# GPRSshield_V2.net
KiCad netlist of a schematic drawn in EAGLE
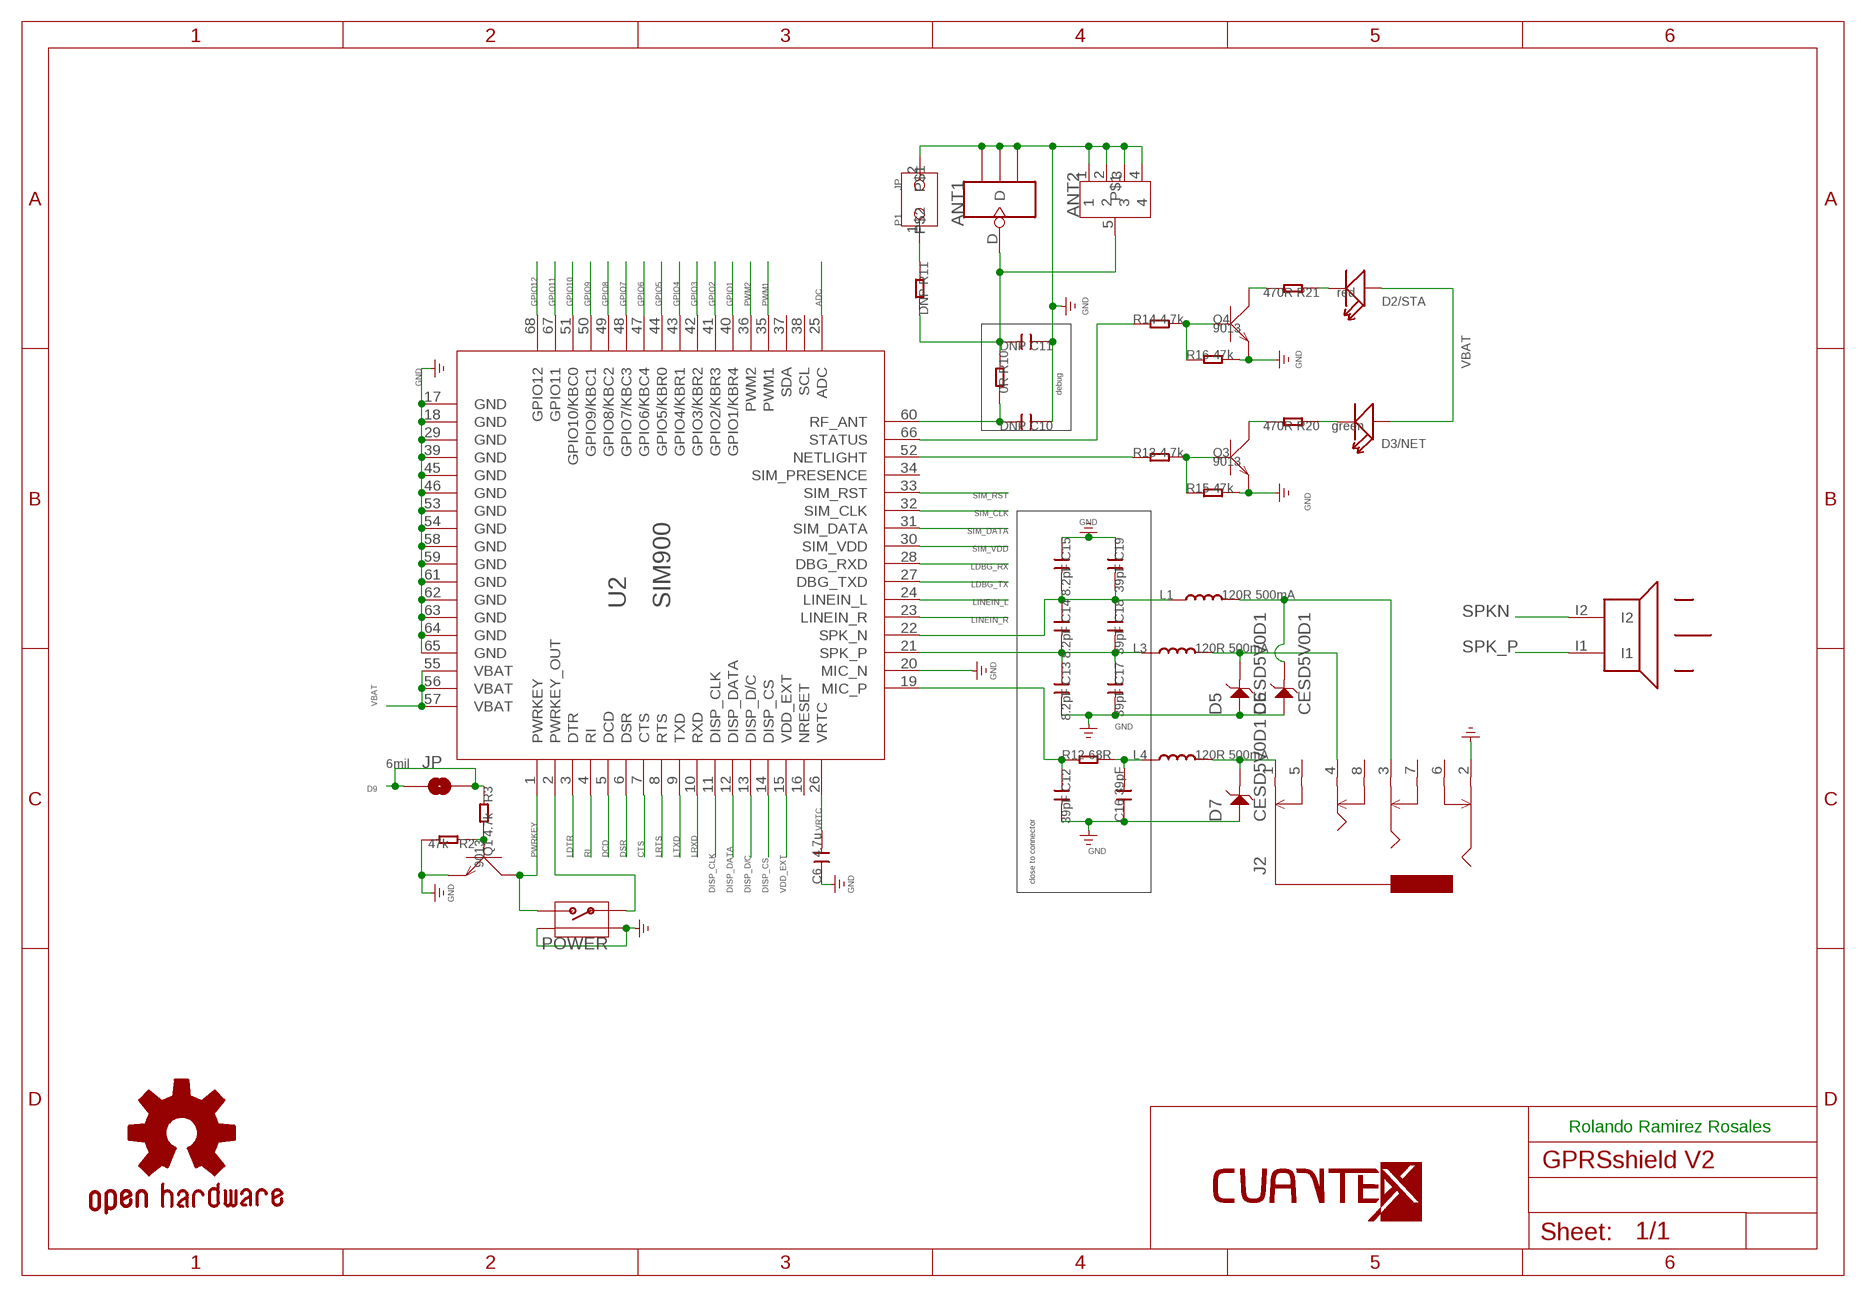
[diagram p0: schematic, sheet 1, part 1 of 2]
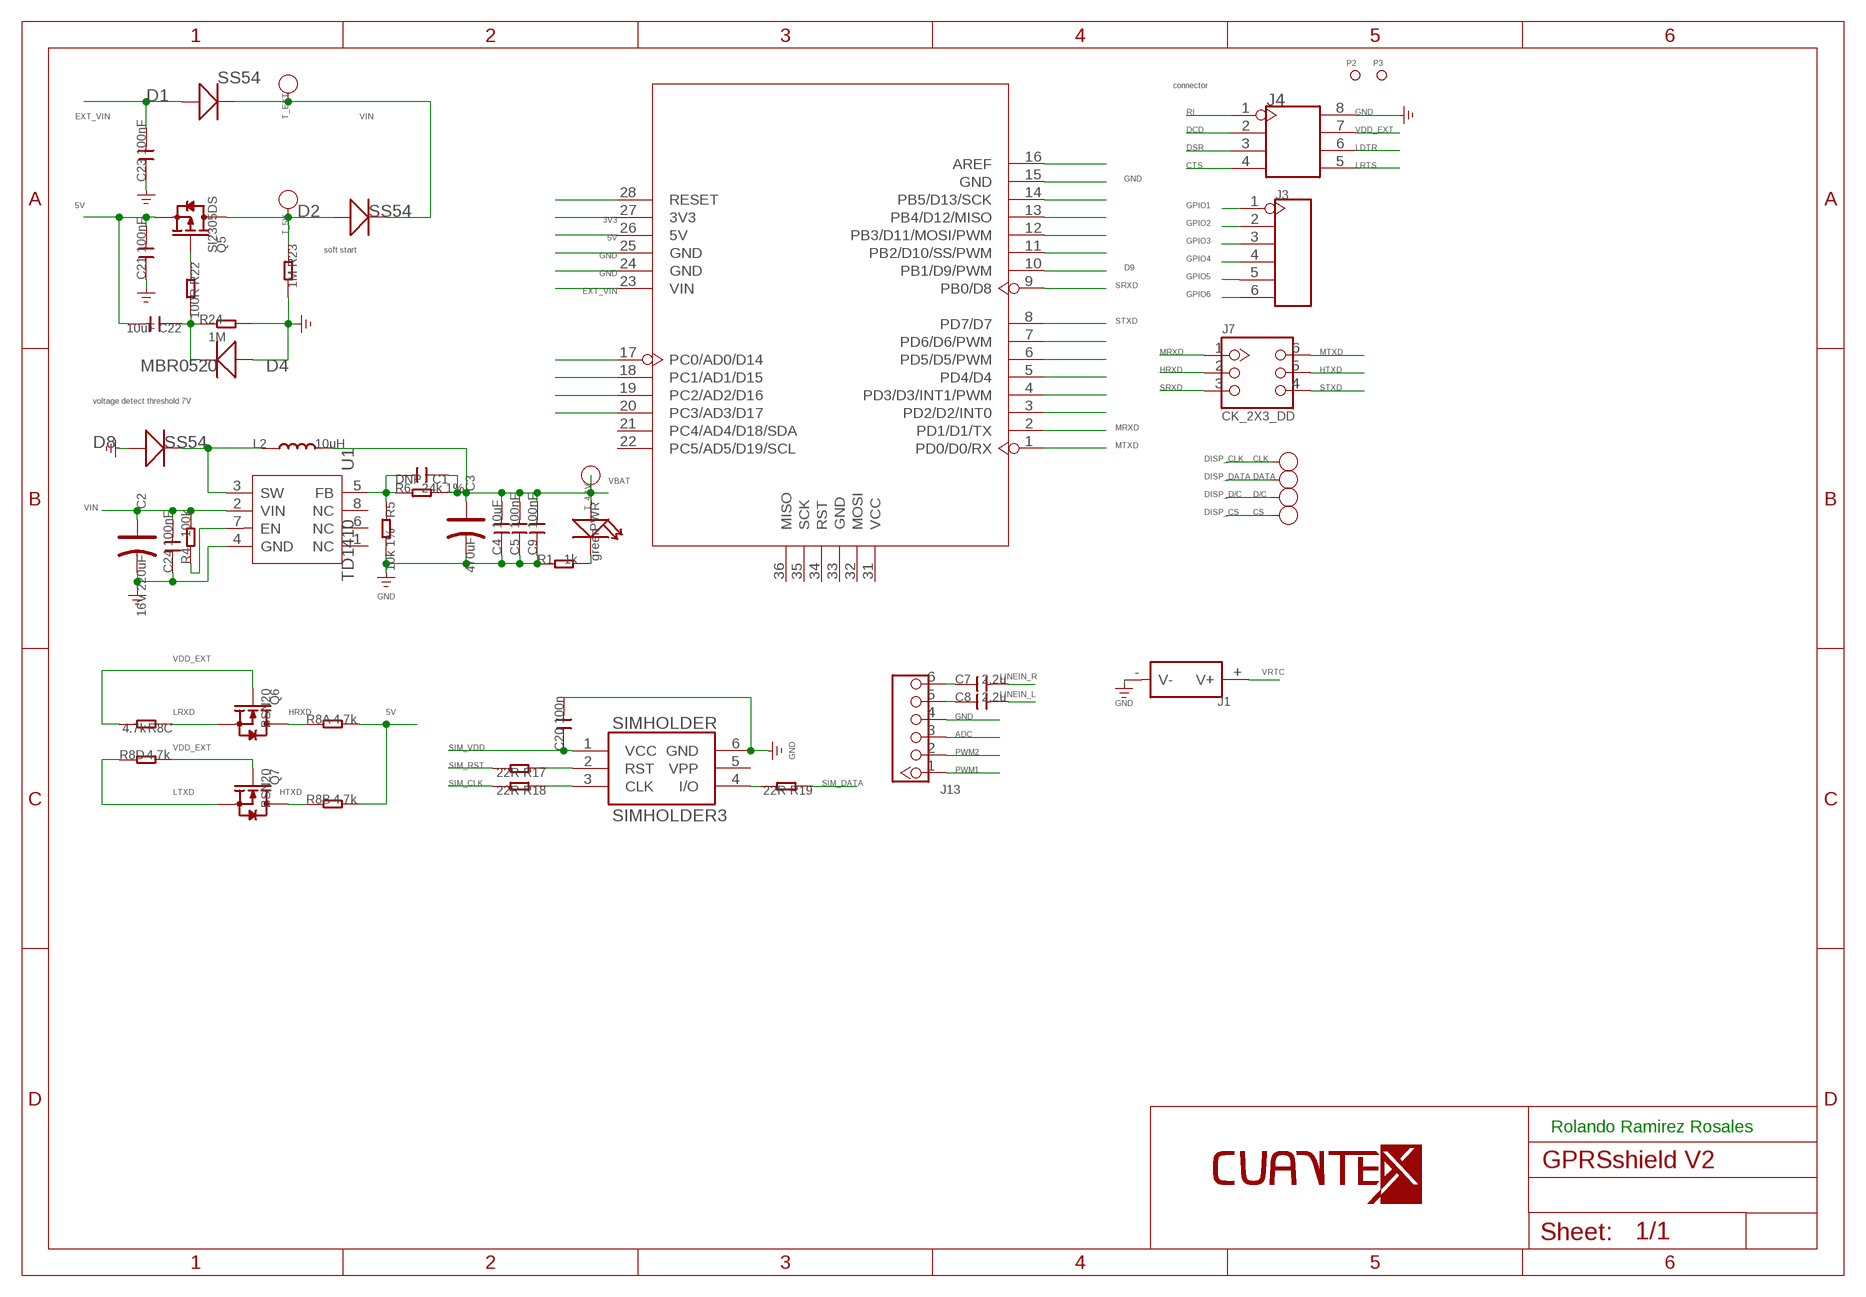
[diagram p1: schematic, sheet 1, part 2 of 2]

(export (version "E")
  (design (tool "Eeschema 10.0.6"))
  (components
    (comp (ref "ANT1")
      (value "ANTENNA-U-FL")
      (footprint "eagle-import:4P-U-FL")
      (libsource (lib "eagle-import") (part "ANTENNA-U-FL"))
    )
    (comp (ref "ANT2")
      (value "ANTENNA-SMA-IPX")
      (footprint "eagle-import:SMA-TO-IPX")
      (libsource (lib "eagle-import") (part "ANTENNA-SMA-IPX"))
    )
    (comp (ref "C1")
      (value "DNP")
      (footprint "eagle-import:C0603")
      (libsource (lib "eagle-import") (part "C-0603"))
    )
    (comp (ref "C2")
      (value "16V 220uF")
      (footprint "eagle-import:ELECTRO-SMD-D-5.6MM")
      (libsource (lib "eagle-import") (part "CAP-ELECTRO-D"))
    )
    (comp (ref "C3")
      (value "470uF")
      (footprint "eagle-import:AVX-D")
      (libsource (lib "eagle-import") (part "CAP-AVX-D"))
    )
    (comp (ref "C4")
      (value "10uF")
      (footprint "eagle-import:C0805")
      (libsource (lib "eagle-import") (part "C-0805"))
    )
    (comp (ref "C5")
      (value "100nF")
      (footprint "eagle-import:C0603")
      (libsource (lib "eagle-import") (part "C-0603"))
    )
    (comp (ref "C6")
      (value "4.7u")
      (footprint "eagle-import:C0805")
      (libsource (lib "eagle-import") (part "C-0805"))
    )
    (comp (ref "C7")
      (value "2.2u")
      (footprint "eagle-import:C0805")
      (libsource (lib "eagle-import") (part "C-0805"))
    )
    (comp (ref "C8")
      (value "2.2u")
      (footprint "eagle-import:C0805")
      (libsource (lib "eagle-import") (part "C-0805"))
    )
    (comp (ref "C9")
      (value "100nF")
      (footprint "eagle-import:C0603")
      (libsource (lib "eagle-import") (part "C-0603"))
    )
    (comp (ref "C10")
      (value "DNP")
      (footprint "eagle-import:C0603")
      (libsource (lib "eagle-import") (part "C-0603"))
    )
    (comp (ref "C11")
      (value "DNP")
      (footprint "eagle-import:C0603")
      (libsource (lib "eagle-import") (part "C-0603"))
    )
    (comp (ref "C12")
      (value "39pF")
      (footprint "eagle-import:C0603")
      (libsource (lib "eagle-import") (part "C-0603"))
    )
    (comp (ref "C13")
      (value "8.2pF")
      (footprint "eagle-import:C0603")
      (libsource (lib "eagle-import") (part "C-0603"))
    )
    (comp (ref "C14")
      (value "8.2pF")
      (footprint "eagle-import:C0603")
      (libsource (lib "eagle-import") (part "C-0603"))
    )
    (comp (ref "C15")
      (value "8.2pF")
      (footprint "eagle-import:C0603")
      (libsource (lib "eagle-import") (part "C-0603"))
    )
    (comp (ref "C16")
      (value "39pF")
      (footprint "eagle-import:C0603")
      (libsource (lib "eagle-import") (part "C-0603"))
    )
    (comp (ref "C17")
      (value "39pF")
      (footprint "eagle-import:C0603")
      (libsource (lib "eagle-import") (part "C-0603"))
    )
    (comp (ref "C18")
      (value "39pF")
      (footprint "eagle-import:C0603")
      (libsource (lib "eagle-import") (part "C-0603"))
    )
    (comp (ref "C19")
      (value "39pF")
      (footprint "eagle-import:C0603")
      (libsource (lib "eagle-import") (part "C-0603"))
    )
    (comp (ref "C20")
      (value "100n")
      (footprint "eagle-import:C0603")
      (libsource (lib "eagle-import") (part "C-0603"))
    )
    (comp (ref "C21")
      (value "100nF")
      (footprint "eagle-import:C0603")
      (libsource (lib "eagle-import") (part "C-0603"))
    )
    (comp (ref "C22")
      (value "10uF")
      (footprint "eagle-import:C0805")
      (libsource (lib "eagle-import") (part "C-0805"))
    )
    (comp (ref "C23")
      (value "100nF")
      (footprint "eagle-import:C0603")
      (libsource (lib "eagle-import") (part "C-0603"))
    )
    (comp (ref "C24")
      (value "100nF")
      (footprint "eagle-import:C0603")
      (libsource (lib "eagle-import") (part "C-0603"))
    )
    (comp (ref "CLK")
      (value "PAD-TEST-POINT-CIRCLE'4545'")
      (footprint "eagle-import:TP_4545")
      (fields (field (name "PARTNO") "DNP"))
      (libsource (lib "eagle-import") (part "PAD-TEST-POINT-CIRCLE'4545'"))
    )
    (comp (ref "CS")
      (value "PAD-TEST-POINT-CIRCLE'4545'")
      (footprint "eagle-import:TP_4545")
      (fields (field (name "PARTNO") "DNP"))
      (libsource (lib "eagle-import") (part "PAD-TEST-POINT-CIRCLE'4545'"))
    )
    (comp (ref "D/C")
      (value "PAD-TEST-POINT-CIRCLE'4545'")
      (footprint "eagle-import:TP_4545")
      (fields (field (name "PARTNO") "DNP"))
      (libsource (lib "eagle-import") (part "PAD-TEST-POINT-CIRCLE'4545'"))
    )
    (comp (ref "D1")
      (value "SS54")
      (footprint "eagle-import:SMB")
      (libsource (lib "eagle-import") (part "D'MBRS240LT3'"))
    )
    (comp (ref "D2")
      (value "SS54")
      (footprint "eagle-import:SMB")
      (libsource (lib "eagle-import") (part "D'MBRS240LT3'"))
    )
    (comp (ref "D2/STA")
      (value "red")
      (footprint "eagle-import:LED-0603")
      (libsource (lib "eagle-import") (part "LED'0603'"))
    )
    (comp (ref "D3/NET")
      (value "green")
      (footprint "eagle-import:LED-0603")
      (libsource (lib "eagle-import") (part "LED'0603'"))
    )
    (comp (ref "D4")
      (value "MBR0520")
      (footprint "eagle-import:SOD123-2.7X1.6")
      (libsource (lib "eagle-import") (part "D'MBR0520LT1'"))
    )
    (comp (ref "D5")
      (value "CESD5V0D1")
      (footprint "eagle-import:SOD123-2.7X1.6")
      (libsource (lib "eagle-import") (part "D-ESD"))
    )
    (comp (ref "D6")
      (value "CESD5V0D1")
      (footprint "eagle-import:SOD123-2.7X1.6")
      (libsource (lib "eagle-import") (part "D-ESD"))
    )
    (comp (ref "D7")
      (value "CESD5V0D1")
      (footprint "eagle-import:SOD123-2.7X1.6")
      (libsource (lib "eagle-import") (part "D-ESD"))
    )
    (comp (ref "D8")
      (value "SS54")
      (footprint "eagle-import:SMB")
      (libsource (lib "eagle-import") (part "D'MBRS240LT3'"))
    )
    (comp (ref "DATA")
      (value "PAD-TEST-POINT-CIRCLE'4545'")
      (footprint "eagle-import:TP_4545")
      (fields (field (name "PARTNO") "DNP"))
      (libsource (lib "eagle-import") (part "PAD-TEST-POINT-CIRCLE'4545'"))
    )
    (comp (ref "GOLD_ORB_SM1")
      (value "OSHWLOGO_GOLD_ORB_SM")
      (footprint "eagle-import:OSHW2")
      (libsource (lib "eagle-import") (part "OSHWLOGO_GOLD_ORB_SM"))
    )
    (comp (ref "J1")
      (value "HOLDER-BAT")
      (footprint "eagle-import:SMD-CR1220-2")
      (libsource (lib "eagle-import") (part "HOLDER-BAT"))
    )
    (comp (ref "J2")
      (value "AUDIO-8P'PJ-3536-L6S'")
      (footprint "eagle-import:8P-3.5-SMD")
      (libsource (lib "eagle-import") (part "AUDIO-8P'PJ-3536-L6S'"))
    )
    (comp (ref "J3")
      (value "HEADER-6P-65/35MIL")
      (footprint "eagle-import:6P-2.54-65_35MIL")
      (libsource (lib "eagle-import") (part "HEADER-6P-65/35MIL"))
    )
    (comp (ref "J4")
      (value "HEADER-2X4P-2.54")
      (footprint "eagle-import:2X4P-2.54")
      (libsource (lib "eagle-import") (part "HEADER-2X4P-2.54"))
    )
    (comp (ref "J7")
      (value "CK_2X3_DD")
      (footprint "eagle-import:CK_2X3")
      (libsource (lib "eagle-import") (part "CK_2X3_DD"))
    )
    (comp (ref "J13")
      (value "HEADER_1X6")
      (footprint "eagle-import:CK_1X6")
      (libsource (lib "eagle-import") (part "HEADER_1X6"))
    )
    (comp (ref "JP")
      (value "PAD-SOLDERJUMPERNC")
      (footprint "eagle-import:2P-SMD-3.3X2")
      (libsource (lib "eagle-import") (part "PAD-SOLDERJUMPERNC"))
    )
    (comp (ref "L1")
      (value "120R 500mA")
      (footprint "eagle-import:L0603")
      (libsource (lib "eagle-import") (part "L'0603'"))
    )
    (comp (ref "L2")
      (value "10uH")
      (footprint "eagle-import:L0630")
      (libsource (lib "eagle-import") (part "L'0630'"))
    )
    (comp (ref "L3")
      (value "120R 500mA")
      (footprint "eagle-import:L0603")
      (libsource (lib "eagle-import") (part "L'0603'"))
    )
    (comp (ref "L4")
      (value "120R 500mA")
      (footprint "eagle-import:L0603")
      (libsource (lib "eagle-import") (part "L'0603'"))
    )
    (comp (ref "P1") (value "JP") (footprint "eagle-import:JP") (libsource (lib "eagle-import") (part "JP")))
    (comp (ref "P2")
      (value "PAD-MARK")
      (footprint "eagle-import:ROUND-MARK-1.0")
      (fields (field (name "PARTNO") "DNP"))
      (libsource (lib "eagle-import") (part "PAD-MARK"))
    )
    (comp (ref "P3")
      (value "PAD-MARK")
      (footprint "eagle-import:ROUND-MARK-1.0")
      (fields (field (name "PARTNO") "DNP"))
      (libsource (lib "eagle-import") (part "PAD-MARK"))
    )
    (comp (ref "POWER")
      (value "BUTTON-4P-REINFORCE'TS-118E'")
      (footprint "eagle-import:4P-SMD-7X3.5X3.5H")
      (libsource (lib "eagle-import") (part "BUTTON-4P-REINFORCE'TS-118E'"))
    )
    (comp (ref "PWR")
      (value "green")
      (footprint "eagle-import:D0603")
      (libsource (lib "eagle-import") (part "007-LED0603"))
    )
    (comp (ref "Q1")
      (value "9013")
      (footprint "eagle-import:SOT23")
      (libsource (lib "eagle-import") (part "TRANSISTOR-NPN-SOT23"))
    )
    (comp (ref "Q3")
      (value "9013")
      (footprint "eagle-import:SOT23")
      (libsource (lib "eagle-import") (part "TRANSISTOR-NPN-SOT23"))
    )
    (comp (ref "Q4")
      (value "9013")
      (footprint "eagle-import:SOT23")
      (libsource (lib "eagle-import") (part "TRANSISTOR-NPN-SOT23"))
    )
    (comp (ref "Q5")
      (value "SI2305DS")
      (footprint "eagle-import:SOT23")
      (libsource (lib "eagle-import") (part "MOSFET-P'SI2323CDS/SI2305DS{lt}BR{gt}'"))
    )
    (comp (ref "Q6")
      (value "BSN20")
      (footprint "eagle-import:SOT23")
      (libsource (lib "eagle-import") (part "MOSFET-N'SOT23'"))
    )
    (comp (ref "Q7")
      (value "BSN20")
      (footprint "eagle-import:SOT23")
      (libsource (lib "eagle-import") (part "MOSFET-N'SOT23'"))
    )
    (comp (ref "R1")
      (value "1k")
      (footprint "eagle-import:R0603")
      (libsource (lib "eagle-import") (part "R-0603"))
    )
    (comp (ref "R2")
      (value "47k")
      (footprint "eagle-import:R0603")
      (libsource (lib "eagle-import") (part "R-0603"))
    )
    (comp (ref "R3")
      (value "4.7k")
      (footprint "eagle-import:R0603")
      (libsource (lib "eagle-import") (part "R-0603"))
    )
    (comp (ref "R4")
      (value "100k")
      (footprint "eagle-import:R0603")
      (libsource (lib "eagle-import") (part "R-0603"))
    )
    (comp (ref "R5")
      (value "10k 1%")
      (footprint "eagle-import:R0603")
      (libsource (lib "eagle-import") (part "R-0603"))
    )
    (comp (ref "R6")
      (value "24k 1%")
      (footprint "eagle-import:R0603")
      (libsource (lib "eagle-import") (part "R-0603"))
    )
    (comp (ref "R8")
      (value "4.7k")
      (footprint "eagle-import:1206-8-3.3X2.4")
      (libsource (lib "eagle-import") (part "R-4R-1206"))
    )
    (comp (ref "R10")
      (value "0R")
      (footprint "eagle-import:R0603")
      (libsource (lib "eagle-import") (part "R-0603"))
    )
    (comp (ref "R11")
      (value "DNP")
      (footprint "eagle-import:R0603")
      (libsource (lib "eagle-import") (part "R-0603"))
    )
    (comp (ref "R12")
      (value "68R")
      (footprint "eagle-import:R0603")
      (libsource (lib "eagle-import") (part "R-0603"))
    )
    (comp (ref "R13")
      (value "4.7k")
      (footprint "eagle-import:R0603")
      (libsource (lib "eagle-import") (part "R-0603"))
    )
    (comp (ref "R14")
      (value "4.7k")
      (footprint "eagle-import:R0603")
      (libsource (lib "eagle-import") (part "R-0603"))
    )
    (comp (ref "R15")
      (value "47k")
      (footprint "eagle-import:R0603")
      (libsource (lib "eagle-import") (part "R-0603"))
    )
    (comp (ref "R16")
      (value "47k")
      (footprint "eagle-import:R0603")
      (libsource (lib "eagle-import") (part "R-0603"))
    )
    (comp (ref "R17")
      (value "22R")
      (footprint "eagle-import:R0603")
      (libsource (lib "eagle-import") (part "R-0603"))
    )
    (comp (ref "R18")
      (value "22R")
      (footprint "eagle-import:R0603")
      (libsource (lib "eagle-import") (part "R-0603"))
    )
    (comp (ref "R19")
      (value "22R")
      (footprint "eagle-import:R0603")
      (libsource (lib "eagle-import") (part "R-0603"))
    )
    (comp (ref "R20")
      (value "470R")
      (footprint "eagle-import:R0603")
      (libsource (lib "eagle-import") (part "R-0603"))
    )
    (comp (ref "R21")
      (value "470R")
      (footprint "eagle-import:R0603")
      (libsource (lib "eagle-import") (part "R-0603"))
    )
    (comp (ref "R22")
      (value "100R")
      (footprint "eagle-import:R0603")
      (libsource (lib "eagle-import") (part "R-0603"))
    )
    (comp (ref "R23")
      (value "1M")
      (footprint "eagle-import:R0603")
      (libsource (lib "eagle-import") (part "R-0603"))
    )
    (comp (ref "R24")
      (value "1M")
      (footprint "eagle-import:R0603")
      (libsource (lib "eagle-import") (part "R-0603"))
    )
    (comp (ref "SIMHOLDER")
      (value "SIMHOLDER3")
      (footprint "eagle-import:SIMHOLDER3")
      (libsource (lib "eagle-import") (part "SIMHOLDER3"))
    )
    (comp (ref "T_4.1V")
      (value "PAD-TEST-POINT-CIRCLE'4545'")
      (footprint "eagle-import:TP_4545")
      (fields (field (name "PARTNO") "DNP") (field (name "PARTNO_1") "DNP"))
      (libsource (lib "eagle-import") (part "PAD-TEST-POINT-CIRCLE'4545'"))
    )
    (comp (ref "T_5V")
      (value "PAD-TEST-POINT-CIRCLE'4545'")
      (footprint "eagle-import:TP_4545")
      (fields (field (name "PARTNO") "DNP") (field (name "PARTNO_1") "DNP"))
      (libsource (lib "eagle-import") (part "PAD-TEST-POINT-CIRCLE'4545'"))
    )
    (comp (ref "T_EXT")
      (value "PAD-TEST-POINT-CIRCLE'4545'")
      (footprint "eagle-import:TP_4545")
      (fields (field (name "PARTNO") "DNP") (field (name "PARTNO_1") "DNP"))
      (libsource (lib "eagle-import") (part "PAD-TEST-POINT-CIRCLE'4545'"))
    )
    (comp (ref "U$4")
      (value "SPEAKER_HETPRO")
      (footprint "eagle-import:SPK_SMD")
      (libsource (lib "eagle-import") (part "SPEAKER_HETPRO"))
    )
    (comp (ref "U$11")
      (value "LOGO-TOP-10MM")
      (footprint "eagle-import:C-000")
      (libsource (lib "eagle-import") (part "LOGO-TOP-10MM"))
    )
    (comp (ref "U$23")
      (value "LOGO-TOP-30MM")
      (footprint "eagle-import:C-1")
      (libsource (lib "eagle-import") (part "LOGO-TOP-30MM"))
    )
    (comp (ref "U1")
      (value "TD1410")
      (footprint "eagle-import:SOP8")
      (libsource (lib "eagle-import") (part "TD1410"))
    )
    (comp (ref "U2")
      (value "SIM900")
      (footprint "eagle-import:SIM900")
      (libsource (lib "eagle-import") (part "SIM900"))
    )
    (comp (ref "U3")
      (value "ARDUINO'W/O-SILK'")
      (footprint "eagle-import:ARDUINO-W_O-SILK")
      (libsource (lib "eagle-import") (part "ARDUINO'W/O-SILK'"))
    )
  )
  (nets
    (net (code "1") (name "/3V3") (class "Default")
      (node (ref "U3") (pin "27") (pinfunction "3V3_27") (pintype "bidirectional"))
    )
    (net (code "2") (name "/5V") (class "Default")
      (node (ref "C21") (pin "2") (pinfunction "2_2") (pintype "passive"))
      (node (ref "C22") (pin "2") (pinfunction "2_2") (pintype "passive"))
      (node (ref "Q5") (pin "2") (pinfunction "S_2") (pintype "passive"))
      (node (ref "R8") (pin "7") (pinfunction "2_7") (pintype "passive"))
      (node (ref "R8") (pin "8") (pinfunction "2_8") (pintype "passive"))
      (node (ref "U3") (pin "26") (pinfunction "5V_26") (pintype "bidirectional"))
    )
    (net (code "3") (name "/ADC") (class "Default")
      (node (ref "J13") (pin "3") (pinfunction "3_3") (pintype "bidirectional"))
      (node (ref "U2") (pin "25") (pinfunction "ADC_25") (pintype "input"))
    )
    (net (code "4") (name "/CTS") (class "Default")
      (node (ref "J4") (pin "4") (pinfunction "4_4") (pintype "bidirectional"))
      (node (ref "U2") (pin "7") (pinfunction "CTS_7") (pintype "output"))
    )
    (net (code "5") (name "/D9") (class "Default")
      (node (ref "JP") (pin "1") (pinfunction "1_1") (pintype "passive"))
      (node (ref "JP") (pin "2") (pinfunction "2_2") (pintype "passive"))
      (node (ref "R3") (pin "1") (pinfunction "1_1") (pintype "passive"))
      (node (ref "U3") (pin "10") (pinfunction "PB1/D9/PWM_10") (pintype "bidirectional"))
    )
    (net (code "6") (name "/DCD") (class "Default")
      (node (ref "J4") (pin "2") (pinfunction "2_2") (pintype "bidirectional"))
      (node (ref "U2") (pin "5") (pinfunction "DCD_5") (pintype "output"))
    )
    (net (code "7") (name "/DISP_CLK") (class "Default")
      (node (ref "CLK") (pin "T") (pinfunction "T_T") (pintype "bidirectional"))
      (node (ref "U2") (pin "11") (pinfunction "DISP_CLK_11") (pintype "output"))
    )
    (net (code "8") (name "/DISP_CS") (class "Default")
      (node (ref "CS") (pin "T") (pinfunction "T_T") (pintype "bidirectional"))
      (node (ref "U2") (pin "14") (pinfunction "DISP_CS_14") (pintype "output"))
    )
    (net (code "9") (name "/DISP_DATA") (class "Default")
      (node (ref "DATA") (pin "T") (pinfunction "T_T") (pintype "bidirectional"))
      (node (ref "U2") (pin "12") (pinfunction "DISP_DATA_12") (pintype "bidirectional"))
    )
    (net (code "10") (name "/DISP_D{slash}C") (class "Default")
      (node (ref "D/C") (pin "T") (pinfunction "T_T") (pintype "bidirectional"))
      (node (ref "U2") (pin "13") (pinfunction "DISP_D/C_13") (pintype "output"))
    )
    (net (code "11") (name "/DSR") (class "Default")
      (node (ref "J4") (pin "3") (pinfunction "3_3") (pintype "bidirectional"))
      (node (ref "U2") (pin "6") (pinfunction "DSR_6") (pintype "output"))
    )
    (net (code "12") (name "/EXT_VIN") (class "Default")
      (node (ref "C23") (pin "2") (pinfunction "2_2") (pintype "passive"))
      (node (ref "D1") (pin "+") (pinfunction "+_+") (pintype "passive"))
      (node (ref "U3") (pin "23") (pinfunction "VIN_23") (pintype "bidirectional"))
    )
    (net (code "13") (name "/GPIO1") (class "Default")
      (node (ref "J3") (pin "1") (pinfunction "1_1") (pintype "bidirectional"))
      (node (ref "U2") (pin "40") (pinfunction "GPIO1/KBR4_40") (pintype "output"))
    )
    (net (code "14") (name "/GPIO2") (class "Default")
      (node (ref "J3") (pin "2") (pinfunction "2_2") (pintype "bidirectional"))
      (node (ref "U2") (pin "41") (pinfunction "GPIO2/KBR3_41") (pintype "output"))
    )
    (net (code "15") (name "/GPIO3") (class "Default")
      (node (ref "J3") (pin "3") (pinfunction "3_3") (pintype "bidirectional"))
      (node (ref "U2") (pin "42") (pinfunction "GPIO3/KBR2_42") (pintype "output"))
    )
    (net (code "16") (name "/GPIO4") (class "Default")
      (node (ref "J3") (pin "4") (pinfunction "4_4") (pintype "bidirectional"))
      (node (ref "U2") (pin "43") (pinfunction "GPIO4/KBR1_43") (pintype "output"))
    )
    (net (code "17") (name "/GPIO5") (class "Default")
      (node (ref "J3") (pin "5") (pinfunction "5_5") (pintype "bidirectional"))
      (node (ref "U2") (pin "44") (pinfunction "GPIO5/KBR0_44") (pintype "output"))
    )
    (net (code "18") (name "/GPIO6") (class "Default")
      (node (ref "J3") (pin "6") (pinfunction "6_6") (pintype "bidirectional"))
      (node (ref "U2") (pin "47") (pinfunction "GPIO6/KBC4_47") (pintype "input"))
    )
    (net (code "19") (name "/GPIO7") (class "Default")
      (node (ref "U2") (pin "48") (pinfunction "GPIO7/KBC3_48") (pintype "bidirectional"))
    )
    (net (code "20") (name "/GPIO8") (class "Default")
      (node (ref "U2") (pin "49") (pinfunction "GPIO8/KBC2_49") (pintype "input"))
    )
    (net (code "21") (name "/GPIO9") (class "Default")
      (node (ref "U2") (pin "50") (pinfunction "GPIO9/KBC1_50") (pintype "input"))
    )
    (net (code "22") (name "/GPIO10") (class "Default")
      (node (ref "U2") (pin "51") (pinfunction "GPIO10/KBC0_51") (pintype "bidirectional"))
    )
    (net (code "23") (name "/GPIO11") (class "Default")
      (node (ref "U2") (pin "67") (pinfunction "GPIO11_67") (pintype "bidirectional"))
    )
    (net (code "24") (name "/GPIO12") (class "Default")
      (node (ref "U2") (pin "68") (pinfunction "GPIO12_68") (pintype "bidirectional"))
    )
    (net (code "25") (name "/HRXD") (class "Default")
      (node (ref "J7") (pin "2") (pinfunction "2_2") (pintype "bidirectional"))
      (node (ref "Q6") (pin "3") (pinfunction "D_3") (pintype "passive"))
      (node (ref "R8") (pin "1") (pinfunction "1_1") (pintype "passive"))
    )
    (net (code "26") (name "/HTXD") (class "Default")
      (node (ref "J7") (pin "5") (pinfunction "5_5") (pintype "bidirectional"))
      (node (ref "Q7") (pin "3") (pinfunction "D_3") (pintype "passive"))
      (node (ref "R8") (pin "2") (pinfunction "1_2") (pintype "passive"))
    )
    (net (code "27") (name "/LDBG_RX") (class "Default")
      (node (ref "U2") (pin "28") (pinfunction "DBG_RXD_28") (pintype "input"))
    )
    (net (code "28") (name "/LDBG_TX") (class "Default")
      (node (ref "U2") (pin "27") (pinfunction "DBG_TXD_27") (pintype "output"))
    )
    (net (code "29") (name "/LDTR") (class "Default")
      (node (ref "J4") (pin "6") (pinfunction "6_6") (pintype "bidirectional"))
      (node (ref "U2") (pin "3") (pinfunction "DTR_3") (pintype "input"))
    )
    (net (code "30") (name "/LINEIN_L") (class "Default")
      (node (ref "C8") (pin "2") (pinfunction "2_2") (pintype "passive"))
      (node (ref "U2") (pin "24") (pinfunction "LINEIN_L_24") (pintype "input"))
    )
    (net (code "31") (name "/LINEIN_R") (class "Default")
      (node (ref "C7") (pin "2") (pinfunction "2_2") (pintype "passive"))
      (node (ref "U2") (pin "23") (pinfunction "LINEIN_R_23") (pintype "input"))
    )
    (net (code "32") (name "/LRTS") (class "Default")
      (node (ref "J4") (pin "5") (pinfunction "5_5") (pintype "bidirectional"))
      (node (ref "U2") (pin "8") (pinfunction "RTS_8") (pintype "input"))
    )
    (net (code "33") (name "/LRXD") (class "Default")
      (node (ref "Q6") (pin "2") (pinfunction "S_2") (pintype "passive"))
      (node (ref "R8") (pin "3") (pinfunction "1_3") (pintype "passive"))
      (node (ref "U2") (pin "10") (pinfunction "RXD_10") (pintype "input"))
    )
    (net (code "34") (name "/LTXD") (class "Default")
      (node (ref "Q7") (pin "2") (pinfunction "S_2") (pintype "passive"))
      (node (ref "R8") (pin "4") (pinfunction "1_4") (pintype "passive"))
      (node (ref "U2") (pin "9") (pinfunction "TXD_9") (pintype "output"))
    )
    (net (code "35") (name "/MRXD") (class "Default")
      (node (ref "J7") (pin "1") (pinfunction "1_1") (pintype "bidirectional"))
      (node (ref "U3") (pin "2") (pinfunction "PD1/D1/TX_2") (pintype "bidirectional"))
    )
    (net (code "36") (name "/MTXD") (class "Default")
      (node (ref "J7") (pin "6") (pinfunction "6_6") (pintype "bidirectional"))
      (node (ref "U3") (pin "1") (pinfunction "PD0/D0/RX_1") (pintype "bidirectional"))
    )
    (net (code "37") (name "/PWM1") (class "Default")
      (node (ref "J13") (pin "1") (pinfunction "1_1") (pintype "bidirectional"))
      (node (ref "U2") (pin "35") (pinfunction "PWM1_35") (pintype "output"))
    )
    (net (code "38") (name "/PWM2") (class "Default")
      (node (ref "J13") (pin "2") (pinfunction "2_2") (pintype "bidirectional"))
      (node (ref "U2") (pin "36") (pinfunction "PWM2_36") (pintype "output"))
    )
    (net (code "39") (name "/PWRKEY") (class "Default")
      (node (ref "POWER") (pin "2") (pinfunction "2_2") (pintype "bidirectional"))
      (node (ref "Q1") (pin "3") (pinfunction "C_3") (pintype "passive"))
      (node (ref "U2") (pin "1") (pinfunction "PWRKEY_1") (pintype "input"))
    )
    (net (code "40") (name "/RI") (class "Default")
      (node (ref "J4") (pin "1") (pinfunction "1_1") (pintype "bidirectional"))
      (node (ref "U2") (pin "4") (pinfunction "RI_4") (pintype "output"))
    )
    (net (code "41") (name "/SIM_CLK") (class "Default")
      (node (ref "R18") (pin "2") (pinfunction "2_2") (pintype "passive"))
      (node (ref "U2") (pin "32") (pinfunction "SIM_CLK_32") (pintype "output"))
    )
    (net (code "42") (name "/SIM_DATA") (class "Default")
      (node (ref "R19") (pin "1") (pinfunction "1_1") (pintype "passive"))
      (node (ref "U2") (pin "31") (pinfunction "SIM_DATA_31") (pintype "bidirectional"))
    )
    (net (code "43") (name "/SIM_RST") (class "Default")
      (node (ref "R17") (pin "2") (pinfunction "2_2") (pintype "passive"))
      (node (ref "U2") (pin "33") (pinfunction "SIM_RST_33") (pintype "output"))
    )
    (net (code "44") (name "/SIM_VDD") (class "Default")
      (node (ref "C20") (pin "1") (pinfunction "1_1") (pintype "passive"))
      (node (ref "SIMHOLDER") (pin "1") (pinfunction "VCC_1") (pintype "bidirectional"))
      (node (ref "U2") (pin "30") (pinfunction "SIM_VDD_30") (pintype "output"))
    )
    (net (code "45") (name "/SPKN") (class "Default")
      (node (ref "D6") (pin "2") (pinfunction "2_2") (pintype "bidirectional"))
      (node (ref "J2") (pin "3") (pinfunction "3_3") (pintype "bidirectional"))
      (node (ref "L1") (pin "2") (pinfunction "2_2") (pintype "passive"))
      (node (ref "U$4") (pin "I2") (pinfunction "I2_I2") (pintype "bidirectional"))
    )
    (net (code "46") (name "/SPK_P") (class "Default")
      (node (ref "D5") (pin "2") (pinfunction "2_2") (pintype "bidirectional"))
      (node (ref "J2") (pin "4") (pinfunction "4_4") (pintype "bidirectional"))
      (node (ref "L3") (pin "2") (pinfunction "2_2") (pintype "passive"))
      (node (ref "U$4") (pin "I1") (pinfunction "I1_I1") (pintype "bidirectional"))
    )
    (net (code "47") (name "/SRXD") (class "Default")
      (node (ref "J7") (pin "3") (pinfunction "3_3") (pintype "bidirectional"))
      (node (ref "U3") (pin "9") (pinfunction "PB0/D8_9") (pintype "bidirectional"))
    )
    (net (code "48") (name "/STXD") (class "Default")
      (node (ref "J7") (pin "4") (pinfunction "4_4") (pintype "bidirectional"))
      (node (ref "U3") (pin "8") (pinfunction "PD7/D7_8") (pintype "bidirectional"))
    )
    (net (code "49") (name "/VBAT") (class "Default")
      (node (ref "C1") (pin "1") (pinfunction "1_1") (pintype "passive"))
      (node (ref "C3") (pin "+") (pinfunction "+_+") (pintype "passive"))
      (node (ref "C4") (pin "2") (pinfunction "2_2") (pintype "passive"))
      (node (ref "C5") (pin "2") (pinfunction "2_2") (pintype "passive"))
      (node (ref "C9") (pin "2") (pinfunction "2_2") (pintype "passive"))
      (node (ref "D2/STA") (pin "+") (pinfunction "+_+") (pintype "passive"))
      (node (ref "D3/NET") (pin "+") (pinfunction "+_+") (pintype "passive"))
      (node (ref "L2") (pin "2") (pinfunction "2_2") (pintype "passive"))
      (node (ref "PWR") (pin "+") (pinfunction "+_+") (pintype "passive"))
      (node (ref "R6") (pin "2") (pinfunction "2_2") (pintype "passive"))
      (node (ref "T_4.1V") (pin "T") (pinfunction "T_T") (pintype "bidirectional"))
      (node (ref "U2") (pin "55") (pinfunction "VBAT_55") (pintype "power_in"))
      (node (ref "U2") (pin "56") (pinfunction "VBAT_56") (pintype "power_in"))
      (node (ref "U2") (pin "57") (pinfunction "VBAT_57") (pintype "power_in"))
    )
    (net (code "50") (name "/VDD_EXT") (class "Default")
      (node (ref "J4") (pin "7") (pinfunction "7_7") (pintype "bidirectional"))
      (node (ref "Q6") (pin "1") (pinfunction "G_1") (pintype "passive"))
      (node (ref "Q7") (pin "1") (pinfunction "G_1") (pintype "passive"))
      (node (ref "R8") (pin "5") (pinfunction "2_5") (pintype "passive"))
      (node (ref "R8") (pin "6") (pinfunction "2_6") (pintype "passive"))
      (node (ref "U2") (pin "15") (pinfunction "VDD_EXT_15") (pintype "output"))
    )
    (net (code "51") (name "/VIN") (class "Default")
      (node (ref "C2") (pin "+") (pinfunction "+_+") (pintype "passive"))
      (node (ref "C24") (pin "2") (pinfunction "2_2") (pintype "passive"))
      (node (ref "D1") (pin "-") (pinfunction "-_-") (pintype "passive"))
      (node (ref "D2") (pin "-") (pinfunction "-_-") (pintype "passive"))
      (node (ref "R4") (pin "2") (pinfunction "2_2") (pintype "passive"))
      (node (ref "T_EXT") (pin "T") (pinfunction "T_T") (pintype "bidirectional"))
      (node (ref "U1") (pin "2") (pinfunction "VIN_2") (pintype "input"))
    )
    (net (code "52") (name "/VRTC") (class "Default")
      (node (ref "C6") (pin "2") (pinfunction "2_2") (pintype "passive"))
      (node (ref "J1") (pin "+") (pinfunction "V+_+") (pintype "bidirectional"))
      (node (ref "U2") (pin "26") (pinfunction "VRTC_26") (pintype "bidirectional"))
    )
    (net (code "53") (name "GND_POWER") (class "Default")
      (node (ref "ANT1") (pin "GND1") (pinfunction "GND1_GND1") (pintype "bidirectional"))
      (node (ref "ANT1") (pin "GND2") (pinfunction "GND2_GND2") (pintype "bidirectional"))
      (node (ref "ANT1") (pin "GND3") (pinfunction "GND3_GND3") (pintype "bidirectional"))
      (node (ref "ANT2") (pin "1") (pinfunction "1_1") (pintype "bidirectional"))
      (node (ref "ANT2") (pin "2") (pinfunction "2_2") (pintype "bidirectional"))
      (node (ref "ANT2") (pin "3") (pinfunction "3_3") (pintype "bidirectional"))
      (node (ref "ANT2") (pin "4") (pinfunction "4_4") (pintype "bidirectional"))
      (node (ref "C10") (pin "1") (pinfunction "1_1") (pintype "passive"))
      (node (ref "C11") (pin "1") (pinfunction "1_1") (pintype "passive"))
      (node (ref "C12") (pin "2") (pinfunction "2_2") (pintype "passive"))
      (node (ref "C13") (pin "2") (pinfunction "2_2") (pintype "passive"))
      (node (ref "C15") (pin "1") (pinfunction "1_1") (pintype "passive"))
      (node (ref "C16") (pin "1") (pinfunction "1_1") (pintype "passive"))
      (node (ref "C17") (pin "2") (pinfunction "2_2") (pintype "passive"))
      (node (ref "C19") (pin "1") (pinfunction "1_1") (pintype "passive"))
      (node (ref "C2") (pin "-") (pinfunction "-_-") (pintype "passive"))
      (node (ref "C20") (pin "2") (pinfunction "2_2") (pintype "passive"))
      (node (ref "C21") (pin "1") (pinfunction "1_1") (pintype "passive"))
      (node (ref "C23") (pin "1") (pinfunction "1_1") (pintype "passive"))
      (node (ref "C24") (pin "1") (pinfunction "1_1") (pintype "passive"))
      (node (ref "C3") (pin "-") (pinfunction "-_-") (pintype "passive"))
      (node (ref "C4") (pin "1") (pinfunction "1_1") (pintype "passive"))
      (node (ref "C5") (pin "1") (pinfunction "1_1") (pintype "passive"))
      (node (ref "C6") (pin "1") (pinfunction "1_1") (pintype "passive"))
      (node (ref "C9") (pin "1") (pinfunction "1_1") (pintype "passive"))
      (node (ref "D4") (pin "1") (pinfunction "+_1") (pintype "passive"))
      (node (ref "D5") (pin "1") (pinfunction "1_1") (pintype "bidirectional"))
      (node (ref "D6") (pin "1") (pinfunction "1_1") (pintype "bidirectional"))
      (node (ref "D7") (pin "1") (pinfunction "1_1") (pintype "bidirectional"))
      (node (ref "D8") (pin "+") (pinfunction "+_+") (pintype "passive"))
      (node (ref "J1") (pin "-") (pinfunction "V-_-") (pintype "bidirectional"))
      (node (ref "J13") (pin "4") (pinfunction "4_4") (pintype "bidirectional"))
      (node (ref "J2") (pin "2") (pinfunction "2_2") (pintype "bidirectional"))
      (node (ref "J4") (pin "8") (pinfunction "8_8") (pintype "bidirectional"))
      (node (ref "P1") (pin "2") (pinfunction "P$2_2") (pintype "bidirectional"))
      (node (ref "POWER") (pin "S1") (pinfunction "S1_S1") (pintype "bidirectional"))
      (node (ref "POWER") (pin "S2") (pinfunction "S2_S2") (pintype "bidirectional"))
      (node (ref "Q1") (pin "2") (pinfunction "E_2") (pintype "passive"))
      (node (ref "Q3") (pin "2") (pinfunction "E_2") (pintype "passive"))
      (node (ref "Q4") (pin "2") (pinfunction "E_2") (pintype "passive"))
      (node (ref "R1") (pin "1") (pinfunction "1_1") (pintype "passive"))
      (node (ref "R15") (pin "2") (pinfunction "2_2") (pintype "passive"))
      (node (ref "R16") (pin "2") (pinfunction "2_2") (pintype "passive"))
      (node (ref "R2") (pin "2") (pinfunction "2_2") (pintype "passive"))
      (node (ref "R23") (pin "2") (pinfunction "2_2") (pintype "passive"))
      (node (ref "R24") (pin "2") (pinfunction "2_2") (pintype "passive"))
      (node (ref "R5") (pin "2") (pinfunction "2_2") (pintype "passive"))
      (node (ref "SIMHOLDER") (pin "6") (pinfunction "GND_6") (pintype "bidirectional"))
      (node (ref "U1") (pin "4") (pinfunction "GND_4") (pintype "power_in"))
      (node (ref "U2") (pin "17") (pinfunction "GND_17") (pintype "power_in"))
      (node (ref "U2") (pin "18") (pinfunction "GND_18") (pintype "power_in"))
      (node (ref "U2") (pin "20") (pinfunction "MIC_N_20") (pintype "input"))
      (node (ref "U2") (pin "29") (pinfunction "GND_29") (pintype "power_in"))
      (node (ref "U2") (pin "39") (pinfunction "GND_39") (pintype "power_in"))
      (node (ref "U2") (pin "45") (pinfunction "GND_45") (pintype "power_in"))
      (node (ref "U2") (pin "46") (pinfunction "GND_46") (pintype "power_in"))
      (node (ref "U2") (pin "53") (pinfunction "GND_53") (pintype "power_in"))
      (node (ref "U2") (pin "54") (pinfunction "GND_54") (pintype "power_in"))
      (node (ref "U2") (pin "58") (pinfunction "GND_58") (pintype "power_in"))
      (node (ref "U2") (pin "59") (pinfunction "GND_59") (pintype "power_in"))
      (node (ref "U2") (pin "61") (pinfunction "GND_61") (pintype "power_in"))
      (node (ref "U2") (pin "62") (pinfunction "GND_62") (pintype "power_in"))
      (node (ref "U2") (pin "63") (pinfunction "GND_63") (pintype "power_in"))
      (node (ref "U2") (pin "64") (pinfunction "GND_64") (pintype "power_in"))
      (node (ref "U2") (pin "65") (pinfunction "GND_65") (pintype "power_in"))
      (node (ref "U3") (pin "15") (pinfunction "GND_15") (pintype "bidirectional"))
      (node (ref "U3") (pin "24") (pinfunction "GND_24") (pintype "bidirectional"))
      (node (ref "U3") (pin "25") (pinfunction "GND_25") (pintype "bidirectional"))
    )
    (net (code "54") (name "Net-(ANT2-P$1)") (class "Default")
      (node (ref "ANT1") (pin "D") (pinfunction "D_D") (pintype "bidirectional"))
      (node (ref "ANT2") (pin "5") (pinfunction "P$1_5") (pintype "bidirectional"))
      (node (ref "C11") (pin "2") (pinfunction "2_2") (pintype "passive"))
      (node (ref "R10") (pin "1") (pinfunction "1_1") (pintype "passive"))
      (node (ref "R11") (pin "2") (pinfunction "2_2") (pintype "passive"))
    )
    (net (code "55") (name "Net-(C7-Pad1)") (class "Default")
      (node (ref "C7") (pin "1") (pinfunction "1_1") (pintype "passive"))
      (node (ref "J13") (pin "6") (pinfunction "6_6") (pintype "bidirectional"))
    )
    (net (code "56") (name "Net-(C8-Pad1)") (class "Default")
      (node (ref "C8") (pin "1") (pinfunction "1_1") (pintype "passive"))
      (node (ref "J13") (pin "5") (pinfunction "5_5") (pintype "bidirectional"))
    )
    (net (code "57") (name "Net-(C16-Pad2)") (class "Default")
      (node (ref "C16") (pin "2") (pinfunction "2_2") (pintype "passive"))
      (node (ref "L4") (pin "1") (pinfunction "1_1") (pintype "passive"))
      (node (ref "R12") (pin "2") (pinfunction "2_2") (pintype "passive"))
    )
    (net (code "58") (name "Net-(D2/STA-Pad-)") (class "Default")
      (node (ref "D2/STA") (pin "-") (pinfunction "-_-") (pintype "passive"))
      (node (ref "R21") (pin "1") (pinfunction "1_1") (pintype "passive"))
    )
    (net (code "59") (name "Net-(D3/NET-Pad-)") (class "Default")
      (node (ref "D3/NET") (pin "-") (pinfunction "-_-") (pintype "passive"))
      (node (ref "R20") (pin "1") (pinfunction "1_1") (pintype "passive"))
    )
    (net (code "60") (name "Net-(D4--)") (class "Default")
      (node (ref "C22") (pin "1") (pinfunction "1_1") (pintype "passive"))
      (node (ref "D4") (pin "2") (pinfunction "-_2") (pintype "passive"))
      (node (ref "R22") (pin "2") (pinfunction "2_2") (pintype "passive"))
      (node (ref "R24") (pin "1") (pinfunction "1_1") (pintype "passive"))
    )
    (net (code "61") (name "Net-(D7-Pad2)") (class "Default")
      (node (ref "D7") (pin "2") (pinfunction "2_2") (pintype "bidirectional"))
      (node (ref "J2") (pin "1") (pinfunction "1_1") (pintype "bidirectional"))
      (node (ref "L4") (pin "2") (pinfunction "2_2") (pintype "passive"))
    )
    (net (code "62") (name "Net-(P1-P$1)") (class "Default")
      (node (ref "P1") (pin "1") (pinfunction "P$1_1") (pintype "bidirectional"))
      (node (ref "R11") (pin "1") (pinfunction "1_1") (pintype "passive"))
    )
    (net (code "63") (name "Net-(PWR-Pad-)") (class "Default")
      (node (ref "PWR") (pin "-") (pinfunction "-_-") (pintype "passive"))
      (node (ref "R1") (pin "2") (pinfunction "2_2") (pintype "passive"))
    )
    (net (code "64") (name "Net-(Q1-B)") (class "Default")
      (node (ref "Q1") (pin "1") (pinfunction "B_1") (pintype "passive"))
      (node (ref "R2") (pin "1") (pinfunction "1_1") (pintype "passive"))
      (node (ref "R3") (pin "2") (pinfunction "2_2") (pintype "passive"))
    )
    (net (code "65") (name "Net-(Q3-B)") (class "Default")
      (node (ref "Q3") (pin "1") (pinfunction "B_1") (pintype "passive"))
      (node (ref "R13") (pin "2") (pinfunction "2_2") (pintype "passive"))
      (node (ref "R15") (pin "1") (pinfunction "1_1") (pintype "passive"))
    )
    (net (code "66") (name "Net-(Q3-C)") (class "Default")
      (node (ref "Q3") (pin "3") (pinfunction "C_3") (pintype "passive"))
      (node (ref "R20") (pin "2") (pinfunction "2_2") (pintype "passive"))
    )
    (net (code "67") (name "Net-(Q4-B)") (class "Default")
      (node (ref "Q4") (pin "1") (pinfunction "B_1") (pintype "passive"))
      (node (ref "R14") (pin "2") (pinfunction "2_2") (pintype "passive"))
      (node (ref "R16") (pin "1") (pinfunction "1_1") (pintype "passive"))
    )
    (net (code "68") (name "Net-(Q4-C)") (class "Default")
      (node (ref "Q4") (pin "3") (pinfunction "C_3") (pintype "passive"))
      (node (ref "R21") (pin "2") (pinfunction "2_2") (pintype "passive"))
    )
    (net (code "69") (name "Net-(Q5-D)") (class "Default")
      (node (ref "D2") (pin "+") (pinfunction "+_+") (pintype "passive"))
      (node (ref "Q5") (pin "3") (pinfunction "D_3") (pintype "passive"))
      (node (ref "R23") (pin "1") (pinfunction "1_1") (pintype "passive"))
      (node (ref "T_5V") (pin "T") (pinfunction "T_T") (pintype "bidirectional"))
    )
    (net (code "70") (name "Net-(Q5-G)") (class "Default")
      (node (ref "Q5") (pin "1") (pinfunction "G_1") (pintype "passive"))
      (node (ref "R22") (pin "1") (pinfunction "1_1") (pintype "passive"))
    )
    (net (code "71") (name "Net-(SIMHOLDER-CLK)") (class "Default")
      (node (ref "R18") (pin "1") (pinfunction "1_1") (pintype "passive"))
      (node (ref "SIMHOLDER") (pin "3") (pinfunction "CLK_3") (pintype "bidirectional"))
    )
    (net (code "72") (name "Net-(SIMHOLDER-I{slash}O)") (class "Default")
      (node (ref "R19") (pin "2") (pinfunction "2_2") (pintype "passive"))
      (node (ref "SIMHOLDER") (pin "4") (pinfunction "I/O_4") (pintype "bidirectional"))
    )
    (net (code "73") (name "Net-(SIMHOLDER-RST)") (class "Default")
      (node (ref "R17") (pin "1") (pinfunction "1_1") (pintype "passive"))
      (node (ref "SIMHOLDER") (pin "2") (pinfunction "RST_2") (pintype "bidirectional"))
    )
    (net (code "74") (name "Net-(U1-EN)") (class "Default")
      (node (ref "R4") (pin "1") (pinfunction "1_1") (pintype "passive"))
      (node (ref "U1") (pin "7") (pinfunction "EN_7") (pintype "input"))
    )
    (net (code "75") (name "Net-(U1-FB)") (class "Default")
      (node (ref "C1") (pin "2") (pinfunction "2_2") (pintype "passive"))
      (node (ref "R5") (pin "1") (pinfunction "1_1") (pintype "passive"))
      (node (ref "R6") (pin "1") (pinfunction "1_1") (pintype "passive"))
      (node (ref "U1") (pin "5") (pinfunction "FB_5") (pintype "input"))
    )
    (net (code "76") (name "Net-(U1-SW)") (class "Default")
      (node (ref "D8") (pin "-") (pinfunction "-_-") (pintype "passive"))
      (node (ref "L2") (pin "1") (pinfunction "1_1") (pintype "passive"))
      (node (ref "U1") (pin "3") (pinfunction "SW_3") (pintype "output"))
    )
    (net (code "77") (name "Net-(U2-MIC_P)") (class "Default")
      (node (ref "C12") (pin "1") (pinfunction "1_1") (pintype "passive"))
      (node (ref "R12") (pin "1") (pinfunction "1_1") (pintype "passive"))
      (node (ref "U2") (pin "19") (pinfunction "MIC_P_19") (pintype "input"))
    )
    (net (code "78") (name "Net-(U2-NETLIGHT)") (class "Default")
      (node (ref "R13") (pin "1") (pinfunction "1_1") (pintype "passive"))
      (node (ref "U2") (pin "52") (pinfunction "NETLIGHT_52") (pintype "output"))
    )
    (net (code "79") (name "Net-(U2-PWRKEY_OUT)") (class "Default")
      (node (ref "POWER") (pin "1") (pinfunction "1_1") (pintype "bidirectional"))
      (node (ref "U2") (pin "2") (pinfunction "PWRKEY_OUT_2") (pintype "output"))
    )
    (net (code "80") (name "Net-(U2-RF_ANT)") (class "Default")
      (node (ref "C10") (pin "2") (pinfunction "2_2") (pintype "passive"))
      (node (ref "R10") (pin "2") (pinfunction "2_2") (pintype "passive"))
      (node (ref "U2") (pin "60") (pinfunction "RF_ANT_60") (pintype "bidirectional"))
    )
    (net (code "81") (name "Net-(U2-SPK_N)") (class "Default")
      (node (ref "C14") (pin "1") (pinfunction "1_1") (pintype "passive"))
      (node (ref "C15") (pin "2") (pinfunction "2_2") (pintype "passive"))
      (node (ref "C18") (pin "1") (pinfunction "1_1") (pintype "passive"))
      (node (ref "C19") (pin "2") (pinfunction "2_2") (pintype "passive"))
      (node (ref "L1") (pin "1") (pinfunction "1_1") (pintype "passive"))
      (node (ref "U2") (pin "22") (pinfunction "SPK_N_22") (pintype "output"))
    )
    (net (code "82") (name "Net-(U2-SPK_P)") (class "Default")
      (node (ref "C13") (pin "1") (pinfunction "1_1") (pintype "passive"))
      (node (ref "C14") (pin "2") (pinfunction "2_2") (pintype "passive"))
      (node (ref "C17") (pin "1") (pinfunction "1_1") (pintype "passive"))
      (node (ref "C18") (pin "2") (pinfunction "2_2") (pintype "passive"))
      (node (ref "L3") (pin "1") (pinfunction "1_1") (pintype "passive"))
      (node (ref "U2") (pin "21") (pinfunction "SPK_P_21") (pintype "output"))
    )
    (net (code "83") (name "Net-(U2-STATUS)") (class "Default")
      (node (ref "R14") (pin "1") (pinfunction "1_1") (pintype "passive"))
      (node (ref "U2") (pin "66") (pinfunction "STATUS_66") (pintype "output"))
    )
    (net (code "84") (name "unconnected-(J2-Pad5)") (class "Default")
      (node (ref "J2") (pin "5") (pinfunction "5_5") (pintype "bidirectional"))
    )
    (net (code "85") (name "unconnected-(J2-Pad6)") (class "Default")
      (node (ref "J2") (pin "6") (pinfunction "6_6") (pintype "bidirectional"))
    )
    (net (code "86") (name "unconnected-(J2-Pad7)") (class "Default")
      (node (ref "J2") (pin "7") (pinfunction "7_7") (pintype "bidirectional"))
    )
    (net (code "87") (name "unconnected-(J2-Pad8)") (class "Default")
      (node (ref "J2") (pin "8") (pinfunction "8_8") (pintype "bidirectional"))
    )
    (net (code "88") (name "unconnected-(SIMHOLDER-VPP-Pad5)") (class "Default")
      (node (ref "SIMHOLDER") (pin "5") (pinfunction "VPP_5") (pintype "bidirectional"))
    )
    (net (code "89") (name "unconnected-(U1-NC-Pad1)") (class "Default")
      (node (ref "U1") (pin "1") (pinfunction "NC_1") (pintype "no_connect"))
    )
    (net (code "90") (name "unconnected-(U1-NC-Pad6)") (class "Default")
      (node (ref "U1") (pin "6") (pinfunction "NC_6") (pintype "no_connect"))
    )
    (net (code "91") (name "unconnected-(U1-NC-Pad8)") (class "Default")
      (node (ref "U1") (pin "8") (pinfunction "NC_8") (pintype "no_connect"))
    )
    (net (code "92") (name "unconnected-(U2-NRESET-Pad16)") (class "Default")
      (node (ref "U2") (pin "16") (pinfunction "NRESET_16") (pintype "input"))
    )
    (net (code "93") (name "unconnected-(U2-SCL-Pad38)") (class "Default")
      (node (ref "U2") (pin "38") (pinfunction "SCL_38") (pintype "output"))
    )
    (net (code "94") (name "unconnected-(U2-SDA-Pad37)") (class "Default")
      (node (ref "U2") (pin "37") (pinfunction "SDA_37") (pintype "bidirectional"))
    )
    (net (code "95") (name "unconnected-(U2-SIM_PRESENCE-Pad34)") (class "Default")
      (node (ref "U2") (pin "34") (pinfunction "SIM_PRESENCE_34") (pintype "input"))
    )
    (net (code "96") (name "unconnected-(U3-AREF-Pad16)") (class "Default")
      (node (ref "U3") (pin "16") (pinfunction "AREF_16") (pintype "bidirectional"))
    )
    (net (code "97") (name "unconnected-(U3-GND-Pad33)") (class "Default")
      (node (ref "U3") (pin "33") (pinfunction "GND_33") (pintype "bidirectional"))
    )
    (net (code "98") (name "unconnected-(U3-MISO-Pad36)") (class "Default")
      (node (ref "U3") (pin "36") (pinfunction "MISO_36") (pintype "bidirectional"))
    )
    (net (code "99") (name "unconnected-(U3-MOSI-Pad32)") (class "Default")
      (node (ref "U3") (pin "32") (pinfunction "MOSI_32") (pintype "bidirectional"))
    )
    (net (code "100") (name "unconnected-(U3-PB2{slash}D10{slash}SS{slash}PWM-Pad11)") (class "Default")
      (node (ref "U3") (pin "11") (pinfunction "PB2/D10/SS/PWM_11") (pintype "bidirectional"))
    )
    (net (code "101") (name "unconnected-(U3-PB3{slash}D11{slash}MOSI{slash}PWM-Pad12)") (class "Default")
      (node (ref "U3") (pin "12") (pinfunction "PB3/D11/MOSI/PWM_12") (pintype "bidirectional"))
    )
    (net (code "102") (name "unconnected-(U3-PB4{slash}D12{slash}MISO-Pad13)") (class "Default")
      (node (ref "U3") (pin "13") (pinfunction "PB4/D12/MISO_13") (pintype "bidirectional"))
    )
    (net (code "103") (name "unconnected-(U3-PB5{slash}D13{slash}SCK-Pad14)") (class "Default")
      (node (ref "U3") (pin "14") (pinfunction "PB5/D13/SCK_14") (pintype "bidirectional"))
    )
    (net (code "104") (name "unconnected-(U3-PC0{slash}AD0{slash}D14-Pad17)") (class "Default")
      (node (ref "U3") (pin "17") (pinfunction "PC0/AD0/D14_17") (pintype "bidirectional"))
    )
    (net (code "105") (name "unconnected-(U3-PC1{slash}AD1{slash}D15-Pad18)") (class "Default")
      (node (ref "U3") (pin "18") (pinfunction "PC1/AD1/D15_18") (pintype "bidirectional"))
    )
    (net (code "106") (name "unconnected-(U3-PC2{slash}AD2{slash}D16-Pad19)") (class "Default")
      (node (ref "U3") (pin "19") (pinfunction "PC2/AD2/D16_19") (pintype "bidirectional"))
    )
    (net (code "107") (name "unconnected-(U3-PC3{slash}AD3{slash}D17-Pad20)") (class "Default")
      (node (ref "U3") (pin "20") (pinfunction "PC3/AD3/D17_20") (pintype "bidirectional"))
    )
    (net (code "108") (name "unconnected-(U3-PC4{slash}AD4{slash}D18{slash}SDA-Pad21)") (class "Default")
      (node (ref "U3") (pin "21") (pinfunction "PC4/AD4/D18/SDA_21") (pintype "bidirectional"))
    )
    (net (code "109") (name "unconnected-(U3-PC5{slash}AD5{slash}D19{slash}SCL-Pad22)") (class "Default")
      (node (ref "U3") (pin "22") (pinfunction "PC5/AD5/D19/SCL_22") (pintype "bidirectional"))
    )
    (net (code "110") (name "unconnected-(U3-PD2{slash}D2{slash}INT0-Pad3)") (class "Default")
      (node (ref "U3") (pin "3") (pinfunction "PD2/D2/INT0_3") (pintype "bidirectional"))
    )
    (net (code "111") (name "unconnected-(U3-PD3{slash}D3{slash}INT1{slash}PWM-Pad4)") (class "Default")
      (node (ref "U3") (pin "4") (pinfunction "PD3/D3/INT1/PWM_4") (pintype "bidirectional"))
    )
    (net (code "112") (name "unconnected-(U3-PD4{slash}D4-Pad5)") (class "Default")
      (node (ref "U3") (pin "5") (pinfunction "PD4/D4_5") (pintype "bidirectional"))
    )
    (net (code "113") (name "unconnected-(U3-PD5{slash}D5{slash}PWM-Pad6)") (class "Default")
      (node (ref "U3") (pin "6") (pinfunction "PD5/D5/PWM_6") (pintype "bidirectional"))
    )
    (net (code "114") (name "unconnected-(U3-PD6{slash}D6{slash}PWM-Pad7)") (class "Default")
      (node (ref "U3") (pin "7") (pinfunction "PD6/D6/PWM_7") (pintype "bidirectional"))
    )
    (net (code "115") (name "unconnected-(U3-RESET-Pad28)") (class "Default")
      (node (ref "U3") (pin "28") (pinfunction "RESET_28") (pintype "bidirectional"))
    )
    (net (code "116") (name "unconnected-(U3-RST-Pad34)") (class "Default")
      (node (ref "U3") (pin "34") (pinfunction "RST_34") (pintype "bidirectional"))
    )
    (net (code "117") (name "unconnected-(U3-SCK-Pad35)") (class "Default")
      (node (ref "U3") (pin "35") (pinfunction "SCK_35") (pintype "bidirectional"))
    )
    (net (code "118") (name "unconnected-(U3-VCC-Pad31)") (class "Default")
      (node (ref "U3") (pin "31") (pinfunction "VCC_31") (pintype "bidirectional"))
    )
  )
)
